# sword.net
KiCad netlist of a schematic drawn in EAGLE
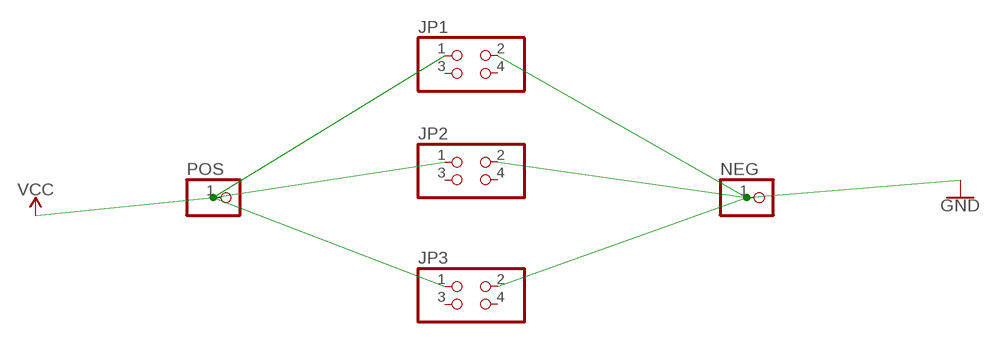
[diagram p0: schematic, sheet 1]

(export (version "E")
  (design (tool "Eeschema 10.0.6"))
  (components
    (comp (ref "JP1")
      (value "PINHD-2X2")
      (footprint "eagle-import:2X02")
      (libsource (lib "eagle-import") (part "PINHD-2X2"))
    )
    (comp (ref "JP2")
      (value "PINHD-2X2")
      (footprint "eagle-import:2X02")
      (libsource (lib "eagle-import") (part "PINHD-2X2"))
    )
    (comp (ref "JP3")
      (value "PINHD-2X2")
      (footprint "eagle-import:2X02")
      (libsource (lib "eagle-import") (part "PINHD-2X2"))
    )
    (comp (ref "NEG")
      (value "PINHD-1X1")
      (footprint "eagle-import:1X01")
      (libsource (lib "eagle-import") (part "PINHD-1X1"))
    )
    (comp (ref "POS")
      (value "PINHD-1X1")
      (footprint "eagle-import:1X01")
      (libsource (lib "eagle-import") (part "PINHD-1X1"))
    )
  )
  (nets
    (net (code "1") (name "GND") (class "Default")
      (node (ref "JP1") (pin "2") (pinfunction "2_2") (pintype "passive"))
      (node (ref "JP2") (pin "2") (pinfunction "2_2") (pintype "passive"))
      (node (ref "JP3") (pin "2") (pinfunction "2_2") (pintype "passive"))
      (node (ref "NEG") (pin "1") (pinfunction "1_1") (pintype "passive"))
    )
    (net (code "2") (name "VCC") (class "Default")
      (node (ref "JP1") (pin "1") (pinfunction "1_1") (pintype "passive"))
      (node (ref "JP2") (pin "1") (pinfunction "1_1") (pintype "passive"))
      (node (ref "JP3") (pin "1") (pinfunction "1_1") (pintype "passive"))
      (node (ref "POS") (pin "1") (pinfunction "1_1") (pintype "passive"))
    )
    (net (code "3") (name "unconnected-(JP1-Pad3)") (class "Default")
      (node (ref "JP1") (pin "3") (pinfunction "3_3") (pintype "passive"))
    )
    (net (code "4") (name "unconnected-(JP1-Pad4)") (class "Default")
      (node (ref "JP1") (pin "4") (pinfunction "4_4") (pintype "passive"))
    )
    (net (code "5") (name "unconnected-(JP2-Pad3)") (class "Default")
      (node (ref "JP2") (pin "3") (pinfunction "3_3") (pintype "passive"))
    )
    (net (code "6") (name "unconnected-(JP2-Pad4)") (class "Default")
      (node (ref "JP2") (pin "4") (pinfunction "4_4") (pintype "passive"))
    )
    (net (code "7") (name "unconnected-(JP3-Pad3)") (class "Default")
      (node (ref "JP3") (pin "3") (pinfunction "3_3") (pintype "passive"))
    )
    (net (code "8") (name "unconnected-(JP3-Pad4)") (class "Default")
      (node (ref "JP3") (pin "4") (pinfunction "4_4") (pintype "passive"))
    )
  )
)
